# Sensor_Acquisition_Board_Rear_rev1.net
KiCad netlist of a schematic drawn in EAGLE
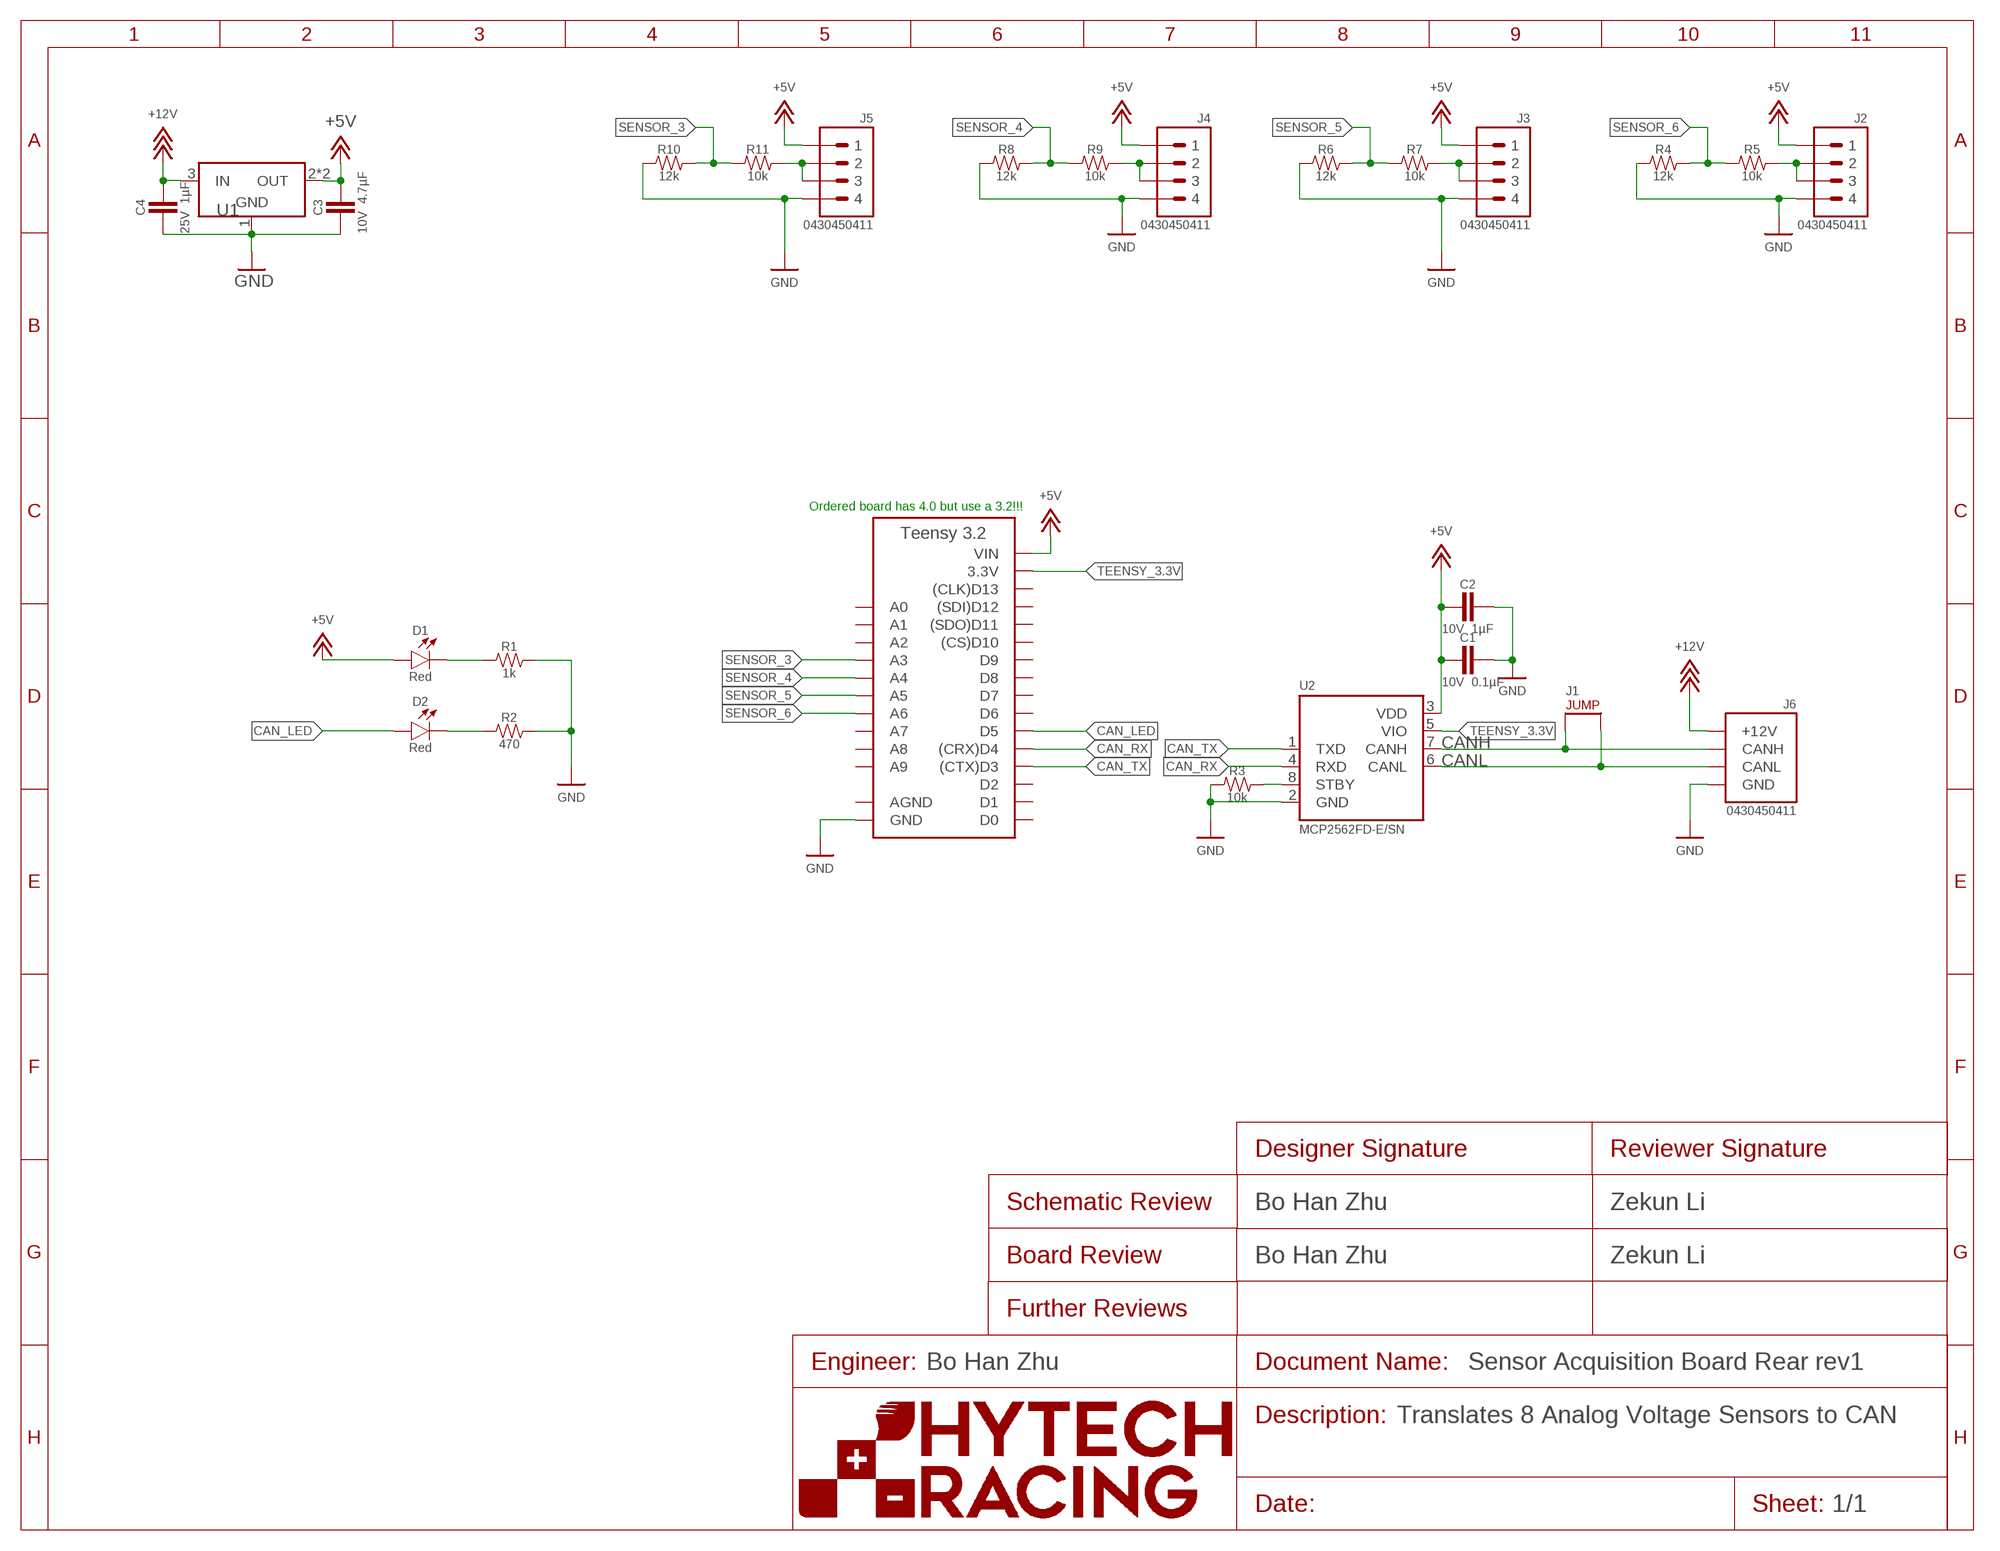
[diagram p0: schematic, sheet 1]

(export (version "E")
  (design (tool "Eeschema 10.0.6"))
  (components
    (comp (ref "A1")
      (value "TEENSY_3.2")
      (footprint "eagle-import:TEENSY_SHORT")
      (libsource (lib "eagle-import") (part "TEENSY_3.2"))
    )
    (comp (ref "C1")
      (value "CAPACITOR_0603_10V_0.1UF")
      (footprint "eagle-import:0603-CAP")
      (fields
        (field (name "CAPACITANCE") "0.1µF")
        (field (name "MANUFACTURER") "Vishay Vitramon")
        (field (name "MPN") "VJ0603Y104JXQPW1BC")
        (field (name "TOLERANCE") "5%")
        (field (name "VOLTAGE") "10V")
      )
      (libsource (lib "eagle-import") (part "CAPACITOR_?_060310V_0.1UF"))
    )
    (comp (ref "C2")
      (value "CAPACITOR_0603_10V_1UF")
      (footprint "eagle-import:0603-CAP")
      (fields
        (field (name "CAPACITANCE") "1µF")
        (field (name "MANUFACTURER") "Yageo")
        (field (name "MPN") "CC0603KRX7R6BB105")
        (field (name "TOLERANCE") "10%")
        (field (name "VOLTAGE") "10V")
      )
      (libsource (lib "eagle-import") (part "CAPACITOR_?_060310V_1UF"))
    )
    (comp (ref "C3")
      (value "CAPACITOR_0603_10V_4.7UF")
      (footprint "eagle-import:0603-CAP")
      (fields
        (field (name "CAPACITANCE") "4.7µF")
        (field (name "MANUFACTURER") "Samsung Electro-Mechanics")
        (field (name "MPN") "CL10A475KP8NNNC")
        (field (name "TOLERANCE") "10%")
        (field (name "VOLTAGE") "10V")
      )
      (libsource (lib "eagle-import") (part "CAPACITOR_?_060310V_4.7UF"))
    )
    (comp (ref "C4")
      (value "CAPACITOR_0603_25V_1UF")
      (footprint "eagle-import:0603-CAP")
      (fields
        (field (name "CAPACITANCE") "1µF")
        (field (name "MANUFACTURER") "Samsung Electro-Mechanics")
        (field (name "MPN") "CL10B105KA8NNNC")
        (field (name "TOLERANCE") "10%")
        (field (name "VOLTAGE") "25V")
      )
      (libsource (lib "eagle-import") (part "CAPACITOR_?_060325V_1UF"))
    )
    (comp (ref "D1")
      (value "LED_0603_RED")
      (footprint "eagle-import:0603-LED")
      (fields
        (field (name "COLOR") "Red")
        (field (name "MANUFACTURER") "Kingbright")
        (field (name "MPN") "APT1608SECK/J3-PRV")
      )
      (libsource (lib "eagle-import") (part "LED_?_0603RED"))
    )
    (comp (ref "D2")
      (value "LED_0603_RED")
      (footprint "eagle-import:0603-LED")
      (fields
        (field (name "COLOR") "Red")
        (field (name "MANUFACTURER") "Kingbright")
        (field (name "MPN") "APT1608SECK/J3-PRV")
      )
      (libsource (lib "eagle-import") (part "LED_?_0603RED"))
    )
    (comp (ref "J1")
      (value "JUMPER_0603_")
      (footprint "eagle-import:0603-RES")
      (fields (field (name "MPN") "RC0603FR-130RL") (field (name "MANUFACTURER") "YAGEO"))
      (libsource (lib "eagle-import") (part "JUMPER_?_0603"))
    )
    (comp (ref "J2")
      (value "CONNECTOR-4_μF_S_RA_")
      (footprint "eagle-import:MOLEX_MICROFIT_SMD_RIGHTANGLE_04_DUAL")
      (fields (field (name "MPN") "0430450411") (field (name "MANUFACTURER") "Molex"))
      (libsource (lib "eagle-import") (part "CONNECTOR-4_?_μF_S_RA"))
    )
    (comp (ref "J3")
      (value "CONNECTOR-4_μF_S_RA_")
      (footprint "eagle-import:MOLEX_MICROFIT_SMD_RIGHTANGLE_04_DUAL")
      (fields (field (name "MPN") "0430450411") (field (name "MANUFACTURER") "Molex"))
      (libsource (lib "eagle-import") (part "CONNECTOR-4_?_μF_S_RA"))
    )
    (comp (ref "J4")
      (value "CONNECTOR-4_μF_S_RA_")
      (footprint "eagle-import:MOLEX_MICROFIT_SMD_RIGHTANGLE_04_DUAL")
      (fields (field (name "MPN") "0430450411") (field (name "MANUFACTURER") "Molex"))
      (libsource (lib "eagle-import") (part "CONNECTOR-4_?_μF_S_RA"))
    )
    (comp (ref "J5")
      (value "CONNECTOR-4_μF_S_RA_")
      (footprint "eagle-import:MOLEX_MICROFIT_SMD_RIGHTANGLE_04_DUAL")
      (fields (field (name "MPN") "0430450411") (field (name "MANUFACTURER") "Molex"))
      (libsource (lib "eagle-import") (part "CONNECTOR-4_?_μF_S_RA"))
    )
    (comp (ref "J6")
      (value "CONNECTOR-CAN_μF_S_RA_")
      (footprint "eagle-import:MOLEX_MICROFIT_SMD_RIGHTANGLE_04_DUAL")
      (fields (field (name "MPN") "0430450411") (field (name "MANUFACTURER") "Molex"))
      (libsource (lib "eagle-import") (part "CONNECTOR-CAN_?_μF_S_RA"))
    )
    (comp (ref "R1")
      (value "RESISTOR_0603_1K")
      (footprint "eagle-import:0603-RES")
      (fields
        (field (name "MANUFACTURER") "Yageo")
        (field (name "MPN") "RC0603FR-071KL")
        (field (name "POWER") "0.1W")
        (field (name "RESISTANCE") "1k")
      )
      (libsource (lib "eagle-import") (part "RESISTOR_?_06031K"))
    )
    (comp (ref "R2")
      (value "RESISTOR_0603_470")
      (footprint "eagle-import:0603-RES")
      (fields
        (field (name "MANUFACTURER") "Panasonic Electronic Components")
        (field (name "MPN") "ERJ-PA3F4700V")
        (field (name "POWER") "0.25W")
        (field (name "RESISTANCE") "470")
      )
      (libsource (lib "eagle-import") (part "RESISTOR_?_0603470"))
    )
    (comp (ref "R3")
      (value "RESISTOR_0603_10K")
      (footprint "eagle-import:0603-RES")
      (fields
        (field (name "MANUFACTURER") "Yageo")
        (field (name "MPN") "RC0603FR-0710KL")
        (field (name "POWER") "0.1W")
        (field (name "RESISTANCE") "10k")
      )
      (libsource (lib "eagle-import") (part "RESISTOR_?_060310K"))
    )
    (comp (ref "R4")
      (value "RESISTOR_0603_12K")
      (footprint "eagle-import:0603-RES")
      (fields
        (field (name "MANUFACTURER") "Yageo")
        (field (name "MPN") "RC0603FR-0712KL")
        (field (name "POWER") "0.1W")
        (field (name "RESISTANCE") "12k")
      )
      (libsource (lib "eagle-import") (part "RESISTOR_?_060312K"))
    )
    (comp (ref "R5")
      (value "RESISTOR_0603_10K")
      (footprint "eagle-import:0603-RES")
      (fields
        (field (name "MANUFACTURER") "Yageo")
        (field (name "MPN") "RC0603FR-0710KL")
        (field (name "POWER") "0.1W")
        (field (name "RESISTANCE") "10k")
      )
      (libsource (lib "eagle-import") (part "RESISTOR_?_060310K"))
    )
    (comp (ref "R6")
      (value "RESISTOR_0603_12K")
      (footprint "eagle-import:0603-RES")
      (fields
        (field (name "MANUFACTURER") "Yageo")
        (field (name "MPN") "RC0603FR-0712KL")
        (field (name "POWER") "0.1W")
        (field (name "RESISTANCE") "12k")
      )
      (libsource (lib "eagle-import") (part "RESISTOR_?_060312K"))
    )
    (comp (ref "R7")
      (value "RESISTOR_0603_10K")
      (footprint "eagle-import:0603-RES")
      (fields
        (field (name "MANUFACTURER") "Yageo")
        (field (name "MPN") "RC0603FR-0710KL")
        (field (name "POWER") "0.1W")
        (field (name "RESISTANCE") "10k")
      )
      (libsource (lib "eagle-import") (part "RESISTOR_?_060310K"))
    )
    (comp (ref "R8")
      (value "RESISTOR_0603_12K")
      (footprint "eagle-import:0603-RES")
      (fields
        (field (name "MANUFACTURER") "Yageo")
        (field (name "MPN") "RC0603FR-0712KL")
        (field (name "POWER") "0.1W")
        (field (name "RESISTANCE") "12k")
      )
      (libsource (lib "eagle-import") (part "RESISTOR_?_060312K"))
    )
    (comp (ref "R9")
      (value "RESISTOR_0603_10K")
      (footprint "eagle-import:0603-RES")
      (fields
        (field (name "MANUFACTURER") "Yageo")
        (field (name "MPN") "RC0603FR-0710KL")
        (field (name "POWER") "0.1W")
        (field (name "RESISTANCE") "10k")
      )
      (libsource (lib "eagle-import") (part "RESISTOR_?_060310K"))
    )
    (comp (ref "R10")
      (value "RESISTOR_0603_12K")
      (footprint "eagle-import:0603-RES")
      (fields
        (field (name "MANUFACTURER") "Yageo")
        (field (name "MPN") "RC0603FR-0712KL")
        (field (name "POWER") "0.1W")
        (field (name "RESISTANCE") "12k")
      )
      (libsource (lib "eagle-import") (part "RESISTOR_?_060312K"))
    )
    (comp (ref "R11")
      (value "RESISTOR_0603_10K")
      (footprint "eagle-import:0603-RES")
      (fields
        (field (name "MANUFACTURER") "Yageo")
        (field (name "MPN") "RC0603FR-0710KL")
        (field (name "POWER") "0.1W")
        (field (name "RESISTANCE") "10k")
      )
      (libsource (lib "eagle-import") (part "RESISTOR_?_060310K"))
    )
    (comp (ref "U1")
      (value "VOLTAGE_REGULATOR_SOT-223_5V")
      (footprint "eagle-import:SOT-223")
      (fields (field (name "MANUFACTURER") "STMicroelectronics") (field (name "MPN") "LDL1117S50R"))
      (libsource (lib "eagle-import") (part "VOLTAGE_REGULATOR_?_SOT-2235V"))
    )
    (comp (ref "U2")
      (value "MCP2562FD")
      (footprint "eagle-import:SOIC-08(NARROW,0.15_)")
      (fields (field (name "MPN") "MCP2562FD-E/SN") (field (name "MANUFACTURER") "Microchip Technology"))
      (libsource (lib "eagle-import") (part "MCP2562FD"))
    )
  )
  (nets
    (net (code "1") (name "+5V") (class "Default")
      (node (ref "A1") (pin "VIN") (pinfunction "VIN_VIN") (pintype "power_in"))
      (node (ref "C1") (pin "2") (pinfunction "2_2") (pintype "passive"))
      (node (ref "C2") (pin "2") (pinfunction "2_2") (pintype "passive"))
      (node (ref "C3") (pin "1") (pinfunction "1_1") (pintype "passive"))
      (node (ref "D1") (pin "2") (pinfunction "A_2") (pintype "passive"))
      (node (ref "J2") (pin "1") (pinfunction "1_1") (pintype "passive"))
      (node (ref "J3") (pin "1") (pinfunction "1_1") (pintype "passive"))
      (node (ref "J4") (pin "1") (pinfunction "1_1") (pintype "passive"))
      (node (ref "J5") (pin "1") (pinfunction "1_1") (pintype "passive"))
      (node (ref "U1") (pin "2") (pinfunction "OUT_2") (pintype "power_in"))
      (node (ref "U1") (pin "4") (pinfunction "OUT_4") (pintype "power_in"))
      (node (ref "U2") (pin "3") (pinfunction "VDD_3") (pintype "power_in"))
    )
    (net (code "2") (name "+12V") (class "Default")
      (node (ref "C4") (pin "1") (pinfunction "1_1") (pintype "passive"))
      (node (ref "J6") (pin "1") (pinfunction "+12V_1") (pintype "power_in"))
      (node (ref "U1") (pin "3") (pinfunction "IN_3") (pintype "power_in"))
    )
    (net (code "3") (name "/AGND") (class "Default")
      (node (ref "A1") (pin "AGND/GND") (pinfunction "AGND_AGND/GND") (pintype "power_in"))
    )
    (net (code "4") (name "/CANH") (class "Default")
      (node (ref "J1") (pin "1") (pinfunction "1_1") (pintype "passive"))
      (node (ref "J6") (pin "4") (pinfunction "CANH_4") (pintype "bidirectional"))
      (node (ref "U2") (pin "7") (pinfunction "CANH_7") (pintype "bidirectional"))
    )
    (net (code "5") (name "/CANL") (class "Default")
      (node (ref "J1") (pin "2") (pinfunction "2_2") (pintype "passive"))
      (node (ref "J6") (pin "3") (pinfunction "CANL_3") (pintype "bidirectional"))
      (node (ref "U2") (pin "6") (pinfunction "CANL_6") (pintype "bidirectional"))
    )
    (net (code "6") (name "CAN_LED") (class "Default")
      (node (ref "A1") (pin "D5") (pinfunction "D5_D5") (pintype "bidirectional"))
      (node (ref "D2") (pin "2") (pinfunction "A_2") (pintype "passive"))
    )
    (net (code "7") (name "CAN_RX") (class "Default")
      (node (ref "A1") (pin "D4") (pinfunction "(CRX)D4_D4") (pintype "bidirectional"))
      (node (ref "U2") (pin "4") (pinfunction "RXD_4") (pintype "output"))
    )
    (net (code "8") (name "CAN_TX") (class "Default")
      (node (ref "A1") (pin "D3") (pinfunction "(CTX)D3_D3") (pintype "bidirectional"))
      (node (ref "U2") (pin "1") (pinfunction "TXD_1") (pintype "input"))
    )
    (net (code "9") (name "GND") (class "Default")
      (node (ref "A1") (pin "GND") (pinfunction "GND_GND") (pintype "power_in"))
      (node (ref "C1") (pin "1") (pinfunction "1_1") (pintype "passive"))
      (node (ref "C2") (pin "1") (pinfunction "1_1") (pintype "passive"))
      (node (ref "C3") (pin "2") (pinfunction "2_2") (pintype "passive"))
      (node (ref "C4") (pin "2") (pinfunction "2_2") (pintype "passive"))
      (node (ref "J2") (pin "4") (pinfunction "4_4") (pintype "passive"))
      (node (ref "J3") (pin "4") (pinfunction "4_4") (pintype "passive"))
      (node (ref "J4") (pin "4") (pinfunction "4_4") (pintype "passive"))
      (node (ref "J5") (pin "4") (pinfunction "4_4") (pintype "passive"))
      (node (ref "J6") (pin "2") (pinfunction "GND_2") (pintype "power_in"))
      (node (ref "R1") (pin "2") (pinfunction "2_2") (pintype "passive"))
      (node (ref "R10") (pin "1") (pinfunction "1_1") (pintype "passive"))
      (node (ref "R2") (pin "2") (pinfunction "2_2") (pintype "passive"))
      (node (ref "R3") (pin "1") (pinfunction "1_1") (pintype "passive"))
      (node (ref "R4") (pin "1") (pinfunction "1_1") (pintype "passive"))
      (node (ref "R6") (pin "1") (pinfunction "1_1") (pintype "passive"))
      (node (ref "R8") (pin "1") (pinfunction "1_1") (pintype "passive"))
      (node (ref "U1") (pin "1") (pinfunction "GND_1") (pintype "power_in"))
      (node (ref "U2") (pin "2") (pinfunction "GND_2") (pintype "power_in"))
    )
    (net (code "10") (name "Net-(D1-C)") (class "Default")
      (node (ref "D1") (pin "1") (pinfunction "C_1") (pintype "passive"))
      (node (ref "R1") (pin "1") (pinfunction "1_1") (pintype "passive"))
    )
    (net (code "11") (name "Net-(D2-C)") (class "Default")
      (node (ref "D2") (pin "1") (pinfunction "C_1") (pintype "passive"))
      (node (ref "R2") (pin "1") (pinfunction "1_1") (pintype "passive"))
    )
    (net (code "12") (name "Net-(J2-Pad2)") (class "Default")
      (node (ref "J2") (pin "2") (pinfunction "2_2") (pintype "passive"))
      (node (ref "J2") (pin "3") (pinfunction "3_3") (pintype "passive"))
      (node (ref "R5") (pin "2") (pinfunction "2_2") (pintype "passive"))
    )
    (net (code "13") (name "Net-(J3-Pad2)") (class "Default")
      (node (ref "J3") (pin "2") (pinfunction "2_2") (pintype "passive"))
      (node (ref "J3") (pin "3") (pinfunction "3_3") (pintype "passive"))
      (node (ref "R7") (pin "2") (pinfunction "2_2") (pintype "passive"))
    )
    (net (code "14") (name "Net-(J4-Pad2)") (class "Default")
      (node (ref "J4") (pin "2") (pinfunction "2_2") (pintype "passive"))
      (node (ref "J4") (pin "3") (pinfunction "3_3") (pintype "passive"))
      (node (ref "R9") (pin "2") (pinfunction "2_2") (pintype "passive"))
    )
    (net (code "15") (name "Net-(J5-Pad2)") (class "Default")
      (node (ref "J5") (pin "2") (pinfunction "2_2") (pintype "passive"))
      (node (ref "J5") (pin "3") (pinfunction "3_3") (pintype "passive"))
      (node (ref "R11") (pin "2") (pinfunction "2_2") (pintype "passive"))
    )
    (net (code "16") (name "Net-(U2-STBY)") (class "Default")
      (node (ref "R3") (pin "2") (pinfunction "2_2") (pintype "passive"))
      (node (ref "U2") (pin "8") (pinfunction "STBY_8") (pintype "passive"))
    )
    (net (code "17") (name "SENSOR_3") (class "Default")
      (node (ref "A1") (pin "D17") (pinfunction "A3_D17") (pintype "bidirectional"))
      (node (ref "R10") (pin "2") (pinfunction "2_2") (pintype "passive"))
      (node (ref "R11") (pin "1") (pinfunction "1_1") (pintype "passive"))
    )
    (net (code "18") (name "SENSOR_4") (class "Default")
      (node (ref "A1") (pin "D18") (pinfunction "A4_D18") (pintype "bidirectional"))
      (node (ref "R8") (pin "2") (pinfunction "2_2") (pintype "passive"))
      (node (ref "R9") (pin "1") (pinfunction "1_1") (pintype "passive"))
    )
    (net (code "19") (name "SENSOR_5") (class "Default")
      (node (ref "A1") (pin "D19") (pinfunction "A5_D19") (pintype "bidirectional"))
      (node (ref "R6") (pin "2") (pinfunction "2_2") (pintype "passive"))
      (node (ref "R7") (pin "1") (pinfunction "1_1") (pintype "passive"))
    )
    (net (code "20") (name "SENSOR_6") (class "Default")
      (node (ref "A1") (pin "D20") (pinfunction "A6_D20") (pintype "bidirectional"))
      (node (ref "R4") (pin "2") (pinfunction "2_2") (pintype "passive"))
      (node (ref "R5") (pin "1") (pinfunction "1_1") (pintype "passive"))
    )
    (net (code "21") (name "TEENSY_3.3V") (class "Default")
      (node (ref "A1") (pin "3.3V") (pinfunction "3.3V_3.3V") (pintype "power_in"))
      (node (ref "U2") (pin "5") (pinfunction "VIO_5") (pintype "power_in"))
    )
    (net (code "22") (name "unconnected-(A1-(CLK)D13-PadD13)") (class "Default")
      (node (ref "A1") (pin "D13") (pinfunction "(CLK)D13_D13") (pintype "bidirectional"))
    )
    (net (code "23") (name "unconnected-(A1-(CS)D10-PadD10)") (class "Default")
      (node (ref "A1") (pin "D10") (pinfunction "(CS)D10_D10") (pintype "bidirectional"))
    )
    (net (code "24") (name "unconnected-(A1-(SDI)D12-PadD12)") (class "Default")
      (node (ref "A1") (pin "D12") (pinfunction "(SDI)D12_D12") (pintype "bidirectional"))
    )
    (net (code "25") (name "unconnected-(A1-(SDO)D11-PadD11)") (class "Default")
      (node (ref "A1") (pin "D11") (pinfunction "(SDO)D11_D11") (pintype "bidirectional"))
    )
    (net (code "26") (name "unconnected-(A1-A0-PadD14)") (class "Default")
      (node (ref "A1") (pin "D14") (pinfunction "A0_D14") (pintype "bidirectional"))
    )
    (net (code "27") (name "unconnected-(A1-A1-PadD15)") (class "Default")
      (node (ref "A1") (pin "D15") (pinfunction "A1_D15") (pintype "bidirectional"))
    )
    (net (code "28") (name "unconnected-(A1-A2-PadD16)") (class "Default")
      (node (ref "A1") (pin "D16") (pinfunction "A2_D16") (pintype "bidirectional"))
    )
    (net (code "29") (name "unconnected-(A1-A7-PadD21)") (class "Default")
      (node (ref "A1") (pin "D21") (pinfunction "A7_D21") (pintype "bidirectional"))
    )
    (net (code "30") (name "unconnected-(A1-A8-PadD22)") (class "Default")
      (node (ref "A1") (pin "D22") (pinfunction "A8_D22") (pintype "bidirectional"))
    )
    (net (code "31") (name "unconnected-(A1-A9-PadD23)") (class "Default")
      (node (ref "A1") (pin "D23") (pinfunction "A9_D23") (pintype "bidirectional"))
    )
    (net (code "32") (name "unconnected-(A1-PadD0)") (class "Default")
      (node (ref "A1") (pin "D0") (pinfunction "D0_D0") (pintype "bidirectional"))
    )
    (net (code "33") (name "unconnected-(A1-PadD1)") (class "Default")
      (node (ref "A1") (pin "D1") (pinfunction "D1_D1") (pintype "bidirectional"))
    )
    (net (code "34") (name "unconnected-(A1-PadD2)") (class "Default")
      (node (ref "A1") (pin "D2") (pinfunction "D2_D2") (pintype "bidirectional"))
    )
    (net (code "35") (name "unconnected-(A1-PadD6)") (class "Default")
      (node (ref "A1") (pin "D6") (pinfunction "D6_D6") (pintype "bidirectional"))
    )
    (net (code "36") (name "unconnected-(A1-PadD7)") (class "Default")
      (node (ref "A1") (pin "D7") (pinfunction "D7_D7") (pintype "bidirectional"))
    )
    (net (code "37") (name "unconnected-(A1-PadD8)") (class "Default")
      (node (ref "A1") (pin "D8") (pinfunction "D8_D8") (pintype "bidirectional"))
    )
    (net (code "38") (name "unconnected-(A1-PadD9)") (class "Default")
      (node (ref "A1") (pin "D9") (pinfunction "D9_D9") (pintype "bidirectional"))
    )
  )
)
